# Sheet2.net
KiCad netlist of a schematic drawn in Altium Designer
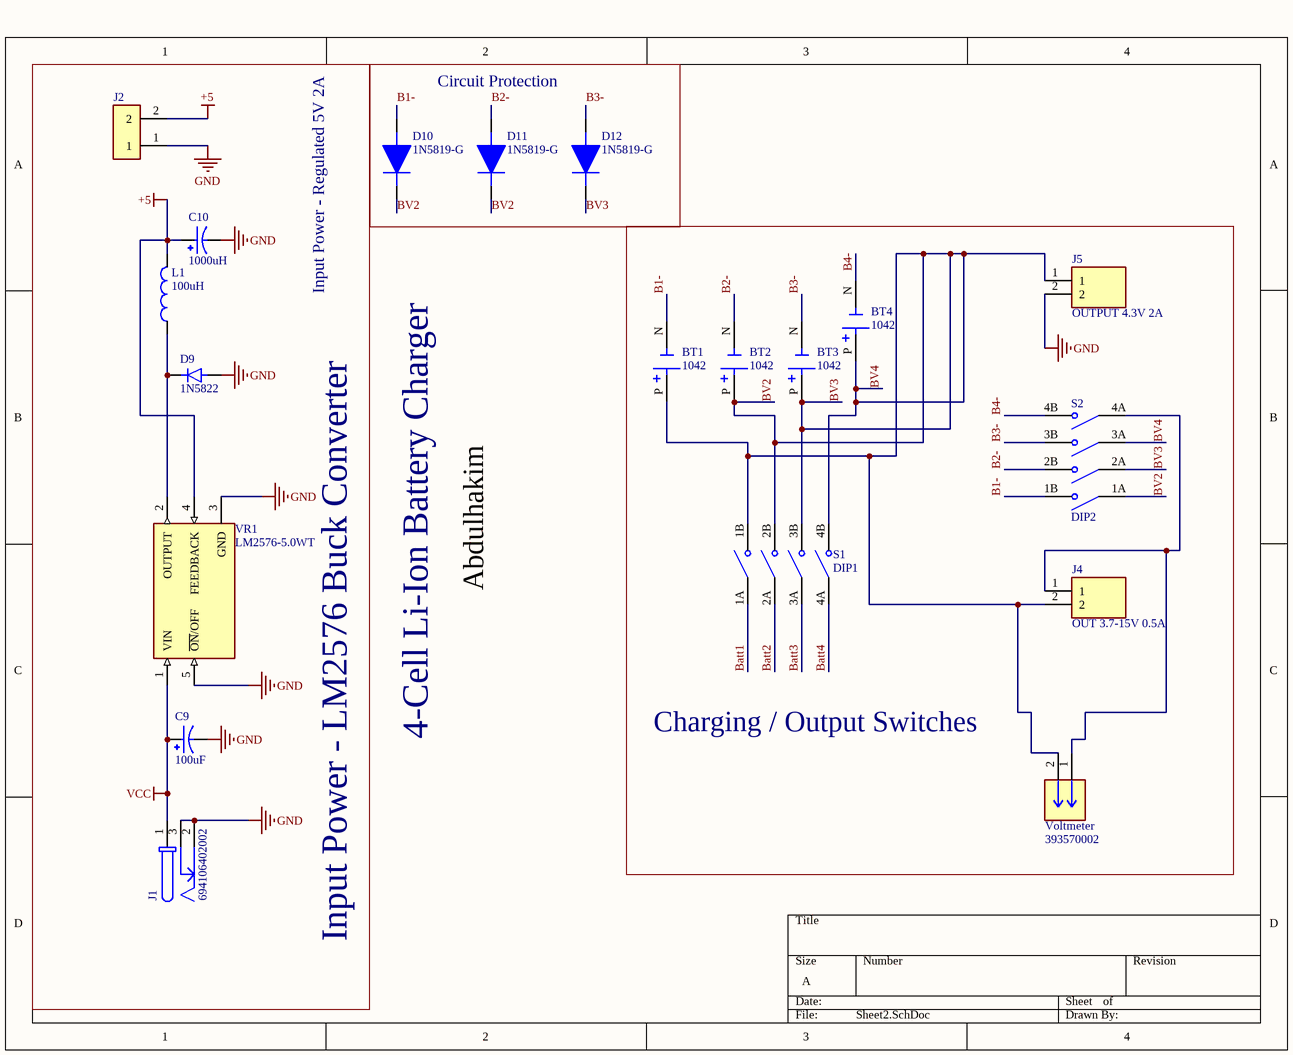
[diagram p0: Sheet2.SchDoc]

(export (version "E")
  (design (tool "Eeschema 10.0.6"))
  (components
    (comp (ref "BT1")
      (value "1042")
      (footprint "BAT_1042")
      (description "SMT Holder for 18650 Battery")
      (fields (field (name "MF") "Keystone Electronics Corp."))
      (libsource (lib "1042") (part "1042"))
    )
    (comp (ref "BT2")
      (value "1042")
      (footprint "BAT_1042")
      (description "SMT Holder for 18650 Battery")
      (fields (field (name "MF") "Keystone Electronics Corp."))
      (libsource (lib "1042") (part "1042"))
    )
    (comp (ref "BT3")
      (value "1042")
      (footprint "BAT_1042")
      (description "SMT Holder for 18650 Battery")
      (fields (field (name "MF") "Keystone Electronics Corp."))
      (libsource (lib "1042") (part "1042"))
    )
    (comp (ref "BT4")
      (value "1042")
      (footprint "BAT_1042")
      (description "SMT Holder for 18650 Battery")
      (fields (field (name "MF") "Keystone Electronics Corp."))
      (libsource (lib "1042") (part "1042"))
    )
    (comp (ref "C9")
      (value "100uF")
      (footprint "CAP_EEEFKV101XAV")
      (description "CAP ALUM 100UF 20% 35V SMD")
      (fields (field (name "MF") "Panasonic") (field (name "MP") "EEEFKV101XAV"))
      (libsource (lib "EEEFKV101XAV") (part "EEEFKV101XAV"))
    )
    (comp (ref "C10")
      (value "1000uH")
      (footprint "CAP_EEEFK0J102AV")
      (description "CAP ALUM 1000UF 20% 6.3V SMD")
      (fields (field (name "MF") "Panasonic") (field (name "MP") "EEEFK0J102AV"))
      (libsource (lib "EEEFK0J102AV") (part "EEEFK0J102AV"))
    )
    (comp (ref "D9")
      (value "1N5822")
      (footprint "DIOAD1990W125L900D530")
      (description "3A, 40V, DÃ¼zlemsel Schottky")
      (fields (field (name "MF") "Taiwan Semiconductor"))
      (libsource (lib "1N5822 (1)") (part "1N5822"))
    )
    (comp (ref "D10")
      (value "1N5819-G")
      (footprint "DIOAD1405W75L465D235")
      (fields (field (name "MF") "ON Semiconductor") (field (name "MP") "1N5819G"))
      (libsource (lib "1N5819-G") (part "1N5819-G"))
    )
    (comp (ref "D11")
      (value "1N5819-G")
      (footprint "DIOAD1405W75L465D235")
      (fields (field (name "MF") "ON Semiconductor") (field (name "MP") "1N5819G"))
      (libsource (lib "1N5819-G") (part "1N5819-G"))
    )
    (comp (ref "D12")
      (value "1N5819-G")
      (footprint "DIOAD1405W75L465D235")
      (fields (field (name "MF") "ON Semiconductor") (field (name "MP") "1N5819G"))
      (libsource (lib "1N5819-G") (part "1N5819-G"))
    )
    (comp (ref "J1")
      (value "694106402002")
      (footprint "694106402002")
      (description "DC Power Jack Connector WR-DC, Male, Vertical, THT, 3 A, 20 V")
      (libsource (lib "Altium Content Vault") (part "DC Power Jack"))
    )
    (comp (ref "J2")
      (value "Input Power - Regulated 5V 2A")
      (footprint "CUI_TB007-508-02BE")
      (description "2 Position Wire to Board Terminal Block Horizontal with Board 0.200 (5.08mm) Through Hole")
      (fields (field (name "MF") "Same Sky") (field (name "MP") "TB00750802BE"))
      (libsource (lib "") (part "TB007-508-02BE_1"))
    )
    (comp (ref "J4")
      (value "OUT 3.7-15V 0.5A")
      (footprint "CUI_TB007-508-02BE")
      (description "2~24 Poles, Screw Type, Horizontal, 5.08 Pitch, 24~12 (AWG), Terminal Block Connector")
      (fields (field (name "MF") "Same Sky") (field (name "MP") "TB007-508-02BE"))
      (libsource (lib "TB007-508-02BE") (part "TB007-508-02BE"))
    )
    (comp (ref "J5")
      (value "OUTPUT 4.3V 2A")
      (footprint "CUI_TB007-508-02BE")
      (description "2~24 Poles, Screw Type, Horizontal, 5.08 Pitch, 24~12 (AWG), Terminal Block Connector")
      (fields (field (name "MF") "Same Sky") (field (name "MP") "TB007-508-02BE"))
      (libsource (lib "TB007-508-02BE") (part "TB007-508-02BE"))
    )
    (comp (ref "L1")
      (value "100uH")
      (footprint "WE-SI_744132")
      (description "L = 49 ÂµH ; IR = 5.8 A; Isat = 2.2 A; RDC = 0.05 â„¦")
      (fields (field (name "MF") "Wurth Elektronik") (field (name "MP") "744132"))
      (libsource (lib "WE-SI") (part "WE-SI"))
    )
    (comp (ref "S1")
      (value "DIP1")
      (footprint "SW_DS01C-254-L-04BE")
      (fields (field (name "MF") "Same Sky") (field (name "MP") "DS01C-254-L-04BE"))
      (libsource (lib "DS01C-254-L-04BE") (part "DS01C-254-L-04BE"))
    )
    (comp (ref "S2")
      (value "DIP2")
      (footprint "SW_DS01C-254-L-04BE")
      (fields (field (name "MF") "Same Sky") (field (name "MP") "DS01C-254-L-04BE"))
      (libsource (lib "DS01C-254-L-04BE") (part "DS01C-254-L-04BE"))
    )
    (comp (ref "Voltmeter")
      (value "393570002")
      (footprint "CONN_393570002_MOL")
      (fields (field (name "MF") "Molex"))
      (libsource (lib "VOLTMERE") (part "393570002"))
    )
    (comp (ref "VR1")
      (value "LM2576-5.0WT")
      (footprint "TO170P1016X444X1572-5")
      (description "Buck Switching Regulator IC Positive Fixed 5V 1 Output 3A TO-220-5")
      (fields (field (name "MF") "Microchip Technology"))
      (libsource (lib "LM2576-5.0WT") (part "LM2576-5.0WT"))
    )
  )
  (nets
    (net (code "1") (name "+5") (class "Default")
      (node (ref "C10") (pin "1") (pinfunction "1_1") (pintype "passive"))
      (node (ref "J2") (pin "2") (pinfunction "2_2") (pintype "passive"))
      (node (ref "L1") (pin "2") (pinfunction "2_2") (pintype "passive"))
      (node (ref "VR1") (pin "4") (pinfunction "FEEDBACK_4") (pintype "input"))
    )
    (net (code "3") (name "/B1-") (class "Default")
      (node (ref "BT1") (pin "N") (pinfunction "NEG_N") (pintype "passive"))
      (node (ref "D10") (pin "2") (pinfunction "A_2") (pintype "bidirectional"))
      (node (ref "S2") (pin "1B") (pinfunction "NO1_1B") (pintype "passive"))
    )
    (net (code "4") (name "/B2-") (class "Default")
      (node (ref "BT2") (pin "N") (pinfunction "NEG_N") (pintype "passive"))
      (node (ref "D11") (pin "2") (pinfunction "A_2") (pintype "bidirectional"))
      (node (ref "S2") (pin "2B") (pinfunction "NO2_2B") (pintype "passive"))
    )
    (net (code "5") (name "/B3-") (class "Default")
      (node (ref "BT3") (pin "N") (pinfunction "NEG_N") (pintype "passive"))
      (node (ref "D12") (pin "2") (pinfunction "A_2") (pintype "bidirectional"))
      (node (ref "S2") (pin "3B") (pinfunction "NO3_3B") (pintype "passive"))
    )
    (net (code "6") (name "/B4-") (class "Default")
      (node (ref "BT4") (pin "N") (pinfunction "NEG_N") (pintype "passive"))
      (node (ref "S2") (pin "4B") (pinfunction "NO4_4B") (pintype "passive"))
    )
    (net (code "7") (name "/BV2") (class "Default")
      (node (ref "BT1") (pin "P") (pinfunction "POS_P") (pintype "passive"))
      (node (ref "BT2") (pin "P") (pinfunction "POS_P") (pintype "passive"))
      (node (ref "BT3") (pin "P") (pinfunction "POS_P") (pintype "passive"))
      (node (ref "BT4") (pin "P") (pinfunction "POS_P") (pintype "passive"))
      (node (ref "D10") (pin "1") (pinfunction "K_1") (pintype "bidirectional"))
      (node (ref "D11") (pin "1") (pinfunction "K_1") (pintype "bidirectional"))
      (node (ref "D12") (pin "1") (pinfunction "K_1") (pintype "bidirectional"))
      (node (ref "J4") (pin "2") (pinfunction "2_2") (pintype "passive"))
      (node (ref "J5") (pin "1") (pinfunction "1_1") (pintype "passive"))
      (node (ref "S1") (pin "1B") (pinfunction "NO1_1B") (pintype "passive"))
      (node (ref "S1") (pin "2B") (pinfunction "NO2_2B") (pintype "passive"))
      (node (ref "S1") (pin "3B") (pinfunction "NO3_3B") (pintype "passive"))
      (node (ref "S1") (pin "4B") (pinfunction "NO4_4B") (pintype "passive"))
      (node (ref "S2") (pin "1A") (pinfunction "COM1_1A") (pintype "passive"))
      (node (ref "S2") (pin "2A") (pinfunction "COM2_2A") (pintype "passive"))
      (node (ref "S2") (pin "3A") (pinfunction "COM3_3A") (pintype "passive"))
      (node (ref "Voltmeter") (pin "2") (pinfunction "2_2") (pintype "passive"))
    )
    (net (code "8") (name "/Batt1") (class "Default")
      (node (ref "S1") (pin "1A") (pinfunction "COM1_1A") (pintype "passive"))
    )
    (net (code "9") (name "/Batt2") (class "Default")
      (node (ref "S1") (pin "2A") (pinfunction "COM2_2A") (pintype "passive"))
    )
    (net (code "10") (name "/Batt3") (class "Default")
      (node (ref "S1") (pin "3A") (pinfunction "COM3_3A") (pintype "passive"))
    )
    (net (code "11") (name "/Batt4") (class "Default")
      (node (ref "S1") (pin "4A") (pinfunction "COM4_4A") (pintype "passive"))
    )
    (net (code "12") (name "GND") (class "Default")
      (node (ref "C10") (pin "2") (pinfunction "2_2") (pintype "passive"))
      (node (ref "C9") (pin "2") (pinfunction "2_2") (pintype "passive"))
      (node (ref "D9") (pin "A") (pinfunction "A_A") (pintype "passive"))
      (node (ref "J1") (pin "2") (pinfunction "2_2") (pintype "passive"))
      (node (ref "J1") (pin "3") (pinfunction "3_3") (pintype "passive"))
      (node (ref "J2") (pin "1") (pinfunction "1_1") (pintype "passive"))
      (node (ref "J5") (pin "2") (pinfunction "2_2") (pintype "passive"))
      (node (ref "VR1") (pin "3") (pinfunction "GND_3") (pintype "power_in"))
      (node (ref "VR1") (pin "5") (pinfunction "~{ON}/OFF_5") (pintype "input"))
    )
    (net (code "13") (name "Net-(D9-K)") (class "Default")
      (node (ref "D9") (pin "C") (pinfunction "K_C") (pintype "passive"))
      (node (ref "L1") (pin "1") (pinfunction "1_1") (pintype "passive"))
      (node (ref "VR1") (pin "2") (pinfunction "OUTPUT_2") (pintype "output"))
    )
    (net (code "14") (name "Net-(S2-COM4)") (class "Default")
      (node (ref "J4") (pin "1") (pinfunction "1_1") (pintype "passive"))
      (node (ref "S2") (pin "4A") (pinfunction "COM4_4A") (pintype "passive"))
      (node (ref "Voltmeter") (pin "1") (pinfunction "1_1") (pintype "passive"))
    )
    (net (code "15") (name "VCC") (class "Default")
      (node (ref "C9") (pin "1") (pinfunction "1_1") (pintype "passive"))
      (node (ref "J1") (pin "1") (pinfunction "1_1") (pintype "passive"))
      (node (ref "VR1") (pin "1") (pinfunction "VIN_1") (pintype "input"))
    )
  )
)
